# Servo_CB_Upgrade.net
KiCad netlist of a schematic drawn in Altium Designer
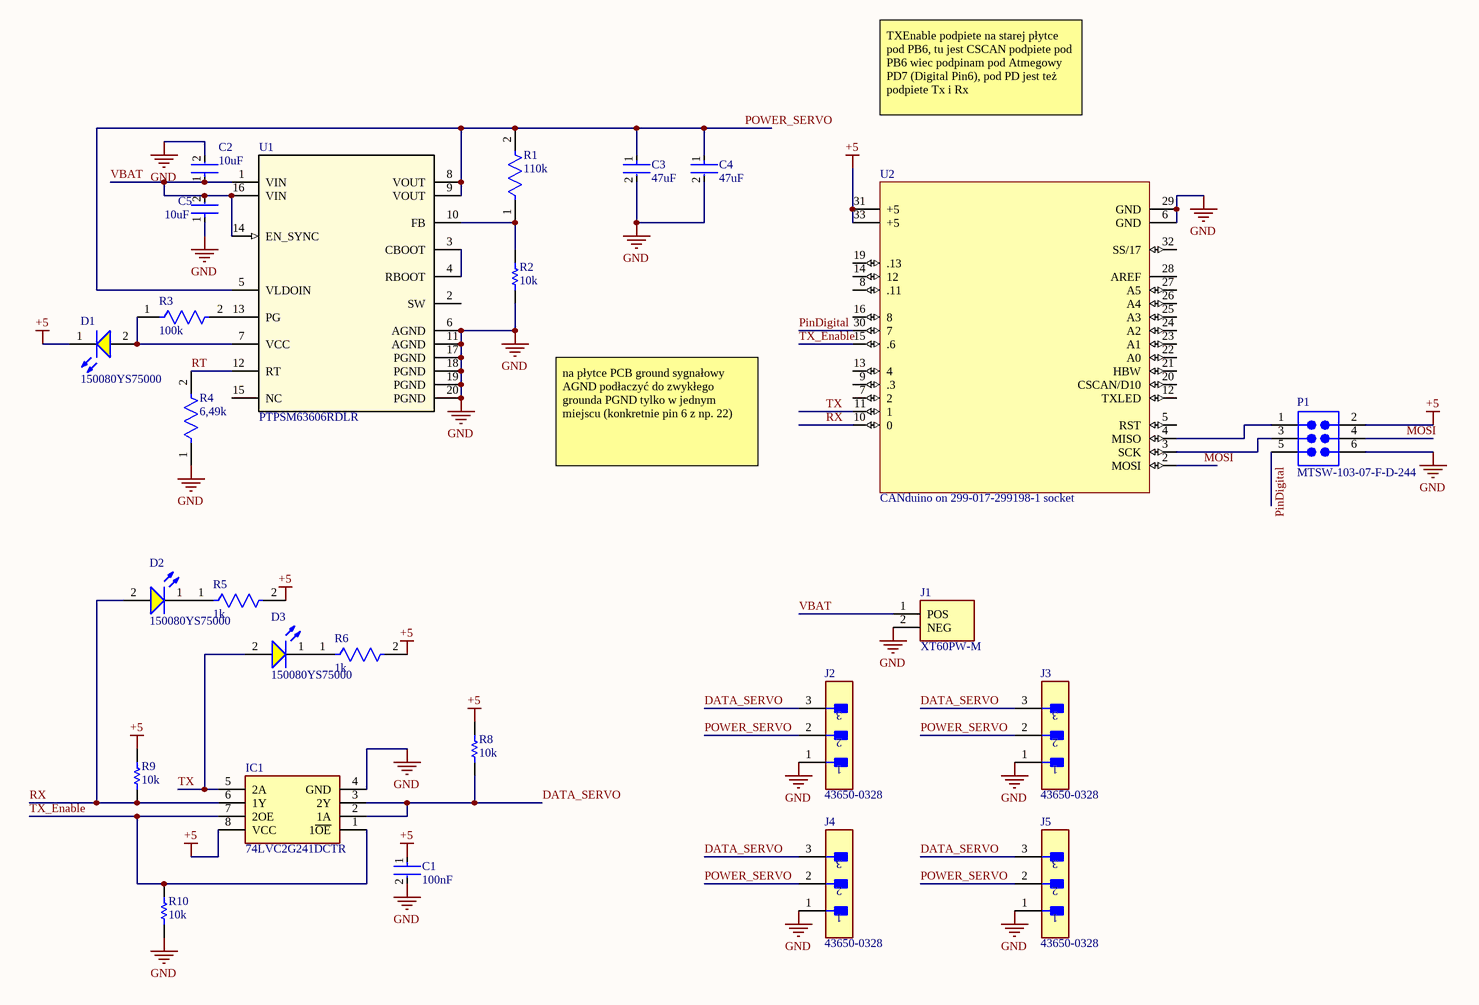
[diagram p0: Servo CB Upgrade.SchDoc]

(export (version "E")
  (design (tool "Eeschema 10.0.6"))
  (components
    (comp (ref "C1")
      (value "100nF")
      (footprint "FP-0805-L_2_01_0_2-W_1_25-IPC_B")
      (description "Automotive Ceramic Capacitor, 0805, 100nF, 10%, X7R, 15%, 100V")
      (fields (field (name "TOLERANCE") "10%") (field (name "VOLTAGE") "100V"))
      (libsource (lib "Altium Content Vault") (part "b4654b650e69147ec39a6b967a45e02"))
    )
    (comp (ref "C2")
      (value "10uF")
      (footprint "FP-CL32-IPC_C")
      (description "Cap Ceramic 10uF 35V X7R ±10% SMD 1210 +125°C Embossed T/R")
      (fields (field (name "VOLTAGE") "35V") (field (name "TOLERANCE") "10%"))
      (libsource (lib "Altium Content Vault") (part "b4654b650e69147ec39a6b967a45e02"))
    )
    (comp (ref "C3")
      (value "47uF")
      (footprint "FP-GRM32E-0_3-0_2-IPC_A")
      (description "Chip Multilayer Ceramic Capacitors for General Purpose, 1210, 47uF, X6S, 22%, 10%, 16V")
      (fields (field (name "VOLTAGE") "16V") (field (name "TOLERANCE") "10%"))
      (libsource (lib "Altium Content Vault") (part "02cd4be3c70576c341d710602a673aa"))
    )
    (comp (ref "C4")
      (value "47uF")
      (footprint "FP-GRM32E-0_3-0_2-IPC_A")
      (description "Chip Multilayer Ceramic Capacitors for General Purpose, 1210, 47uF, X6S, 22%, 10%, 16V")
      (fields (field (name "VOLTAGE") "16V") (field (name "TOLERANCE") "10%"))
      (libsource (lib "Altium Content Vault") (part "02cd4be3c70576c341d710602a673aa"))
    )
    (comp (ref "C5")
      (value "10uF")
      (footprint "FP-CL32-IPC_C")
      (description "Cap Ceramic 10uF 35V X7R ±10% SMD 1210 +125°C Embossed T/R")
      (fields (field (name "VOLTAGE") "35V") (field (name "TOLERANCE") "10%"))
      (libsource (lib "Altium Content Vault") (part "b4654b650e69147ec39a6b967a45e02"))
    )
    (comp (ref "D1")
      (value "150080YS75000")
      (footprint "WL-SMCW_0805_150080xx75000")
      (description "2 V Yellow LED 2012 (0805) SMD, Wurth Elektronik WL-SMCW 150080YS75000")
      (libsource (lib "Altium Content Vault") (part "LED_Yellow_2A-1K"))
    )
    (comp (ref "D2")
      (value "150080YS75000")
      (footprint "WL-SMCW_0805_150080xx75000")
      (description "2 V Yellow LED 2012 (0805) SMD, Wurth Elektronik WL-SMCW 150080YS75000")
      (libsource (lib "Altium Content Vault") (part "LED_Yellow_2A-1K"))
    )
    (comp (ref "D3")
      (value "150080YS75000")
      (footprint "WL-SMCW_0805_150080xx75000")
      (description "2 V Yellow LED 2012 (0805) SMD, Wurth Elektronik WL-SMCW 150080YS75000")
      (libsource (lib "Altium Content Vault") (part "LED_Yellow_2A-1K"))
    )
    (comp (ref "IC1")
      (value "74LVC2G241DCTR")
      (footprint "SamacSys:SOP65P400X130-8N")
      (description "Integrated Circuit")
      (libsource (lib "SamacSys") (part "74LVC2G241DCTR"))
    )
    (comp (ref "J1")
      (value "XT60PW-M")
      (footprint "AMASS_XT60PW-M:AMASS_XT60PW-M")
      (description "Socket, DC supply, male, PIN: 2")
      (fields (field (name "MF") "AMASS"))
      (libsource (lib "XT60PW-M") (part "XT60PW-M"))
    )
    (comp (ref "J2")
      (value "43650-0328")
      (footprint "FP-43650-0328-MFG")
      (description "43650-0328 Connector Header HDR 3 POS 3mm Solder ST Thru-Hole 3 Terminal 1 Port Micro-Fit 3.0 Tray")
      (libsource (lib "Altium Content Vault") (part "0d3f023dd272f625e17a2be33dea85f"))
    )
    (comp (ref "J3")
      (value "43650-0328")
      (footprint "FP-43650-0328-MFG")
      (description "43650-0328 Connector Header HDR 3 POS 3mm Solder ST Thru-Hole 3 Terminal 1 Port Micro-Fit 3.0 Tray")
      (libsource (lib "Altium Content Vault") (part "0d3f023dd272f625e17a2be33dea85f"))
    )
    (comp (ref "J4")
      (value "43650-0328")
      (footprint "FP-43650-0328-MFG")
      (description "43650-0328 Connector Header HDR 3 POS 3mm Solder ST Thru-Hole 3 Terminal 1 Port Micro-Fit 3.0 Tray")
      (libsource (lib "Altium Content Vault") (part "0d3f023dd272f625e17a2be33dea85f"))
    )
    (comp (ref "J5")
      (value "43650-0328")
      (footprint "FP-43650-0328-MFG")
      (description "43650-0328 Connector Header HDR 3 POS 3mm Solder ST Thru-Hole 3 Terminal 1 Port Micro-Fit 3.0 Tray")
      (libsource (lib "Altium Content Vault") (part "0d3f023dd272f625e17a2be33dea85f"))
    )
    (comp (ref "P1")
      (value "MTSW-103-07-F-D-244")
      (footprint "SMTC-MTSW-103-07-X-D-244")
      (fields (field (name "MANUFACTURER") "Samtec"))
      (libsource (lib "Altium Content Vault") (part "SMTC-MTSW-103-07-X-D-244"))
    )
    (comp (ref "R1")
      (value "110k")
      (footprint "FP-AC0603-IPC_A")
      (description "RES 110KΩ 1.00% 0.1W 0603")
      (fields (field (name "TOLERANCE") "1%"))
      (libsource (lib "Altium Content Vault") (part "1029c3af85768c4190bb7ad29bc67b5"))
    )
    (comp (ref "R2")
      (value "10k")
      (footprint "RESC1608X55X25ML10T15")
      (description "Resistor, 10 KOhm, +/- 5%, 100 mW, -55 to 155 degC, 0603 (1608 Metric), RoHS, Tape and Reel")
      (fields (field (name "MANUFACTURER") "Yageo") (field (name "TOLERANCE") "5%"))
      (libsource (lib "Altium Content Vault") (part "RES-2"))
    )
    (comp (ref "R3")
      (value "100k")
      (footprint "FP-AC0603-MFG")
      (description "RES 100KΩ 1.00% 0.1W 0603")
      (fields (field (name "TOLERANCE") "1%"))
      (libsource (lib "Altium Content Vault") (part "1029c3af85768c4190bb7ad29bc67b5"))
    )
    (comp (ref "R4")
      (value "6,49k")
      (footprint "FP-CRCW0603-e3-IPC_A")
      (description "RES Thick Film, 6.49kΩ, 1%, 0.1W, 100ppm/°C, 0603")
      (fields (field (name "TOLERANCE") "1%"))
      (libsource (lib "Altium Content Vault") (part "1029c3af85768c4190bb7ad29bc67b5"))
    )
    (comp (ref "R5")
      (value "1k")
      (footprint "FP-RC0603-0_55-IPC_C")
      (description "RES 1K OHM 1% 1/10W 0603")
      (fields (field (name "TOLERANCE") "1%"))
      (libsource (lib "Altium Content Vault") (part "1029c3af85768c4190bb7ad29bc67b5"))
    )
    (comp (ref "R6")
      (value "1k")
      (footprint "FP-RC0603-0_55-IPC_C")
      (description "RES 1K OHM 1% 1/10W 0603")
      (fields (field (name "TOLERANCE") "1%"))
      (libsource (lib "Altium Content Vault") (part "1029c3af85768c4190bb7ad29bc67b5"))
    )
    (comp (ref "R8")
      (value "10k")
      (footprint "RESC1608X55X25ML10T15")
      (description "Resistor, 10 KOhm, +/- 5%, 100 mW, -55 to 155 degC, 0603 (1608 Metric), RoHS, Tape and Reel")
      (fields (field (name "MANUFACTURER") "Yageo") (field (name "TOLERANCE") "5%"))
      (libsource (lib "Altium Content Vault") (part "RES-2"))
    )
    (comp (ref "R9")
      (value "10k")
      (footprint "RESC1608X55X25ML10T15")
      (description "Resistor, 10 KOhm, +/- 5%, 100 mW, -55 to 155 degC, 0603 (1608 Metric), RoHS, Tape and Reel")
      (fields (field (name "MANUFACTURER") "Yageo") (field (name "TOLERANCE") "5%"))
      (libsource (lib "Altium Content Vault") (part "RES-2"))
    )
    (comp (ref "R10")
      (value "10k")
      (footprint "RESC1608X55X25ML10T15")
      (description "Resistor, 10 KOhm, +/- 5%, 100 mW, -55 to 155 degC, 0603 (1608 Metric), RoHS, Tape and Reel")
      (fields (field (name "MANUFACTURER") "Yageo") (field (name "TOLERANCE") "5%"))
      (libsource (lib "Altium Content Vault") (part "RES-2"))
    )
    (comp (ref "U1")
      (value "PTPSM63606RDLR")
      (footprint "RDL0020A-MFG")
      (description "No Description Available")
      (libsource (lib "PTPSM63606RDLR") (part "PTPSM63606RDLR"))
    )
    (comp (ref "U2")
      (value "CANduino on 299-017-299198-1 socket")
      (footprint "CANduino on 299-017-299198-1 socket")
      (description "CANduino board without pins 1, 17, 18 and 34 due to socket specification")
      (libsource (lib "CANduino") (part "CANduino on 299-017-299198-1 socket"))
    )
  )
  (nets
    (net (code "1") (name "+5") (class "Default")
      (node (ref "C1") (pin "1") (pinfunction "1_1") (pintype "passive"))
      (node (ref "D1") (pin "1") (pinfunction "K_1") (pintype "passive"))
      (node (ref "IC1") (pin "8") (pinfunction "VCC_8") (pintype "passive"))
      (node (ref "P1") (pin "2") (pinfunction "2_2") (pintype "passive"))
      (node (ref "R5") (pin "2") (pinfunction "2_2") (pintype "passive"))
      (node (ref "R6") (pin "2") (pinfunction "2_2") (pintype "passive"))
      (node (ref "R8") (pin "2") (pinfunction "2_2") (pintype "passive"))
      (node (ref "R9") (pin "2") (pinfunction "2_2") (pintype "passive"))
      (node (ref "U2") (pin "31") (pinfunction "+5_31") (pintype "power_in"))
      (node (ref "U2") (pin "33") (pinfunction "+5_33") (pintype "power_in"))
    )
    (net (code "2") (name "/DATA_SERVO") (class "Default")
      (node (ref "IC1") (pin "2") (pinfunction "1A_2") (pintype "passive"))
      (node (ref "IC1") (pin "3") (pinfunction "2Y_3") (pintype "passive"))
      (node (ref "J2") (pin "3") (pinfunction "3_3") (pintype "passive"))
      (node (ref "J3") (pin "3") (pinfunction "3_3") (pintype "passive"))
      (node (ref "J4") (pin "3") (pinfunction "3_3") (pintype "passive"))
      (node (ref "J5") (pin "3") (pinfunction "3_3") (pintype "passive"))
      (node (ref "R8") (pin "1") (pinfunction "1_1") (pintype "passive"))
    )
    (net (code "3") (name "/MOSI") (class "Default")
      (node (ref "P1") (pin "4") (pinfunction "4_4") (pintype "passive"))
      (node (ref "U2") (pin "2") (pinfunction "MOSI_2") (pintype "bidirectional"))
    )
    (net (code "4") (name "/POWER_SERVO") (class "Default")
      (node (ref "C3") (pin "1") (pinfunction "1_1") (pintype "passive"))
      (node (ref "C4") (pin "1") (pinfunction "1_1") (pintype "passive"))
      (node (ref "J2") (pin "2") (pinfunction "2_2") (pintype "passive"))
      (node (ref "J3") (pin "2") (pinfunction "2_2") (pintype "passive"))
      (node (ref "J4") (pin "2") (pinfunction "2_2") (pintype "passive"))
      (node (ref "J5") (pin "2") (pinfunction "2_2") (pintype "passive"))
      (node (ref "R1") (pin "2") (pinfunction "2_2") (pintype "passive"))
      (node (ref "U1") (pin "5") (pinfunction "VLDOIN_5") (pintype "passive"))
      (node (ref "U1") (pin "8") (pinfunction "VOUT_8") (pintype "passive"))
      (node (ref "U1") (pin "9") (pinfunction "VOUT_9") (pintype "passive"))
    )
    (net (code "5") (name "/PinDigital") (class "Default")
      (node (ref "P1") (pin "5") (pinfunction "5_5") (pintype "passive"))
      (node (ref "U2") (pin "30") (pinfunction "7_30") (pintype "bidirectional"))
    )
    (net (code "6") (name "/RT") (class "Default")
      (node (ref "R4") (pin "2") (pinfunction "2_2") (pintype "passive"))
      (node (ref "U1") (pin "12") (pinfunction "RT_12") (pintype "passive"))
    )
    (net (code "7") (name "/RX") (class "Default")
      (node (ref "D2") (pin "2") (pinfunction "A_2") (pintype "passive"))
      (node (ref "IC1") (pin "6") (pinfunction "1Y_6") (pintype "passive"))
      (node (ref "R9") (pin "1") (pinfunction "1_1") (pintype "passive"))
      (node (ref "U2") (pin "10") (pinfunction "0_10") (pintype "bidirectional"))
    )
    (net (code "8") (name "/TX") (class "Default")
      (node (ref "D3") (pin "2") (pinfunction "A_2") (pintype "passive"))
      (node (ref "IC1") (pin "5") (pinfunction "2A_5") (pintype "passive"))
      (node (ref "U2") (pin "11") (pinfunction "1_11") (pintype "bidirectional"))
    )
    (net (code "9") (name "/TX_Enable") (class "Default")
      (node (ref "IC1") (pin "1") (pinfunction "1~{OE}_1") (pintype "passive"))
      (node (ref "IC1") (pin "7") (pinfunction "2OE_7") (pintype "passive"))
      (node (ref "R10") (pin "2") (pinfunction "2_2") (pintype "passive"))
      (node (ref "U2") (pin "15") (pinfunction ".6_15") (pintype "bidirectional"))
    )
    (net (code "10") (name "/VBAT") (class "Default")
      (node (ref "C2") (pin "1") (pinfunction "1_1") (pintype "passive"))
      (node (ref "C5") (pin "2") (pinfunction "2_2") (pintype "passive"))
      (node (ref "J1") (pin "1") (pinfunction "POS_1") (pintype "passive"))
      (node (ref "U1") (pin "1") (pinfunction "VIN_1") (pintype "power_in"))
      (node (ref "U1") (pin "14") (pinfunction "EN_SYNC_14") (pintype "input"))
      (node (ref "U1") (pin "16") (pinfunction "VIN_16") (pintype "power_in"))
    )
    (net (code "11") (name "GND") (class "Default")
      (node (ref "C1") (pin "2") (pinfunction "2_2") (pintype "passive"))
      (node (ref "C2") (pin "2") (pinfunction "2_2") (pintype "passive"))
      (node (ref "C3") (pin "2") (pinfunction "2_2") (pintype "passive"))
      (node (ref "C4") (pin "2") (pinfunction "2_2") (pintype "passive"))
      (node (ref "C5") (pin "1") (pinfunction "1_1") (pintype "passive"))
      (node (ref "IC1") (pin "4") (pinfunction "GND_4") (pintype "passive"))
      (node (ref "J1") (pin "2") (pinfunction "NEG_2") (pintype "passive"))
      (node (ref "J2") (pin "1") (pinfunction "1_1") (pintype "passive"))
      (node (ref "J3") (pin "1") (pinfunction "1_1") (pintype "passive"))
      (node (ref "J4") (pin "1") (pinfunction "1_1") (pintype "passive"))
      (node (ref "J5") (pin "1") (pinfunction "1_1") (pintype "passive"))
      (node (ref "P1") (pin "6") (pinfunction "6_6") (pintype "passive"))
      (node (ref "R10") (pin "1") (pinfunction "1_1") (pintype "passive"))
      (node (ref "R2") (pin "1") (pinfunction "1_1") (pintype "passive"))
      (node (ref "R4") (pin "1") (pinfunction "1_1") (pintype "passive"))
      (node (ref "U1") (pin "11") (pinfunction "AGND_11") (pintype "power_in"))
      (node (ref "U1") (pin "17") (pinfunction "PGND_17") (pintype "power_in"))
      (node (ref "U1") (pin "18") (pinfunction "PGND_18") (pintype "power_in"))
      (node (ref "U1") (pin "19") (pinfunction "PGND_19") (pintype "power_in"))
      (node (ref "U1") (pin "20") (pinfunction "PGND_20") (pintype "power_in"))
      (node (ref "U1") (pin "6") (pinfunction "AGND_6") (pintype "power_in"))
      (node (ref "U2") (pin "29") (pinfunction "GND_29") (pintype "passive"))
      (node (ref "U2") (pin "6") (pinfunction "GND_6") (pintype "passive"))
    )
    (net (code "12") (name "Net-(D1-A)") (class "Default")
      (node (ref "D1") (pin "2") (pinfunction "A_2") (pintype "passive"))
      (node (ref "R3") (pin "1") (pinfunction "1_1") (pintype "passive"))
      (node (ref "U1") (pin "7") (pinfunction "VCC_7") (pintype "passive"))
    )
    (net (code "13") (name "Net-(D2-K)") (class "Default")
      (node (ref "D2") (pin "1") (pinfunction "K_1") (pintype "passive"))
      (node (ref "R5") (pin "1") (pinfunction "1_1") (pintype "passive"))
    )
    (net (code "14") (name "Net-(D3-K)") (class "Default")
      (node (ref "D3") (pin "1") (pinfunction "K_1") (pintype "passive"))
      (node (ref "R6") (pin "1") (pinfunction "1_1") (pintype "passive"))
    )
    (net (code "15") (name "Net-(U1-CBOOT)") (class "Default")
      (node (ref "U1") (pin "3") (pinfunction "CBOOT_3") (pintype "passive"))
      (node (ref "U1") (pin "4") (pinfunction "RBOOT_4") (pintype "passive"))
    )
    (net (code "16") (name "Net-(U1-FB)") (class "Default")
      (node (ref "R1") (pin "1") (pinfunction "1_1") (pintype "passive"))
      (node (ref "R2") (pin "2") (pinfunction "2_2") (pintype "passive"))
      (node (ref "U1") (pin "10") (pinfunction "FB_10") (pintype "passive"))
    )
    (net (code "17") (name "Net-(U1-PG)") (class "Default")
      (node (ref "R3") (pin "2") (pinfunction "2_2") (pintype "passive"))
      (node (ref "U1") (pin "13") (pinfunction "PG_13") (pintype "open_collector"))
    )
    (net (code "18") (name "Net-(U2-MISO)") (class "Default")
      (node (ref "P1") (pin "1") (pinfunction "1_1") (pintype "passive"))
      (node (ref "U2") (pin "4") (pinfunction "MISO_4") (pintype "bidirectional"))
    )
    (net (code "19") (name "Net-(U2-SCK)") (class "Default")
      (node (ref "P1") (pin "3") (pinfunction "3_3") (pintype "passive"))
      (node (ref "U2") (pin "3") (pinfunction "SCK_3") (pintype "bidirectional"))
    )
    (net (code "20") (name "unconnected-(U1-NC-Pad15)") (class "Default")
      (node (ref "U1") (pin "15") (pinfunction "NC_15") (pintype "passive"))
    )
    (net (code "21") (name "unconnected-(U1-SW-Pad2)") (class "Default")
      (node (ref "U1") (pin "2") (pinfunction "SW_2") (pintype "passive"))
    )
    (net (code "22") (name "unconnected-(U2-.3-Pad9)") (class "Default")
      (node (ref "U2") (pin "9") (pinfunction ".3_9") (pintype "bidirectional"))
    )
    (net (code "23") (name "unconnected-(U2-.11-Pad8)") (class "Default")
      (node (ref "U2") (pin "8") (pinfunction ".11_8") (pintype "bidirectional"))
    )
    (net (code "24") (name "unconnected-(U2-.13-Pad19)") (class "Default")
      (node (ref "U2") (pin "19") (pinfunction ".13_19") (pintype "bidirectional"))
    )
    (net (code "25") (name "unconnected-(U2-2-Pad7)") (class "Default")
      (node (ref "U2") (pin "7") (pinfunction "2_7") (pintype "bidirectional"))
    )
    (net (code "26") (name "unconnected-(U2-4-Pad13)") (class "Default")
      (node (ref "U2") (pin "13") (pinfunction "4_13") (pintype "bidirectional"))
    )
    (net (code "27") (name "unconnected-(U2-8-Pad16)") (class "Default")
      (node (ref "U2") (pin "16") (pinfunction "8_16") (pintype "bidirectional"))
    )
    (net (code "28") (name "unconnected-(U2-12-Pad14)") (class "Default")
      (node (ref "U2") (pin "14") (pinfunction "12_14") (pintype "bidirectional"))
    )
    (net (code "29") (name "unconnected-(U2-A0-Pad22)") (class "Default")
      (node (ref "U2") (pin "22") (pinfunction "A0_22") (pintype "bidirectional"))
    )
    (net (code "30") (name "unconnected-(U2-A1-Pad23)") (class "Default")
      (node (ref "U2") (pin "23") (pinfunction "A1_23") (pintype "bidirectional"))
    )
    (net (code "31") (name "unconnected-(U2-A2-Pad24)") (class "Default")
      (node (ref "U2") (pin "24") (pinfunction "A2_24") (pintype "bidirectional"))
    )
    (net (code "32") (name "unconnected-(U2-A3-Pad25)") (class "Default")
      (node (ref "U2") (pin "25") (pinfunction "A3_25") (pintype "bidirectional"))
    )
    (net (code "33") (name "unconnected-(U2-A4-Pad26)") (class "Default")
      (node (ref "U2") (pin "26") (pinfunction "A4_26") (pintype "bidirectional"))
    )
    (net (code "34") (name "unconnected-(U2-A5-Pad27)") (class "Default")
      (node (ref "U2") (pin "27") (pinfunction "A5_27") (pintype "bidirectional"))
    )
    (net (code "35") (name "unconnected-(U2-AREF-Pad28)") (class "Default")
      (node (ref "U2") (pin "28") (pinfunction "AREF_28") (pintype "passive"))
    )
    (net (code "36") (name "unconnected-(U2-CSCAN{slash}D10-Pad20)") (class "Default")
      (node (ref "U2") (pin "20") (pinfunction "CSCAN/D10_20") (pintype "bidirectional"))
    )
    (net (code "37") (name "unconnected-(U2-HBW-Pad21)") (class "Default")
      (node (ref "U2") (pin "21") (pinfunction "HBW_21") (pintype "bidirectional"))
    )
    (net (code "38") (name "unconnected-(U2-RST-Pad5)") (class "Default")
      (node (ref "U2") (pin "5") (pinfunction "RST_5") (pintype "bidirectional"))
    )
    (net (code "39") (name "unconnected-(U2-SS{slash}17-Pad32)") (class "Default")
      (node (ref "U2") (pin "32") (pinfunction "SS/17_32") (pintype "bidirectional"))
    )
    (net (code "40") (name "unconnected-(U2-TXLED-Pad12)") (class "Default")
      (node (ref "U2") (pin "12") (pinfunction "TXLED_12") (pintype "bidirectional"))
    )
  )
)
